# twomics_sw_led.net
KiCad netlist of a schematic drawn in EAGLE
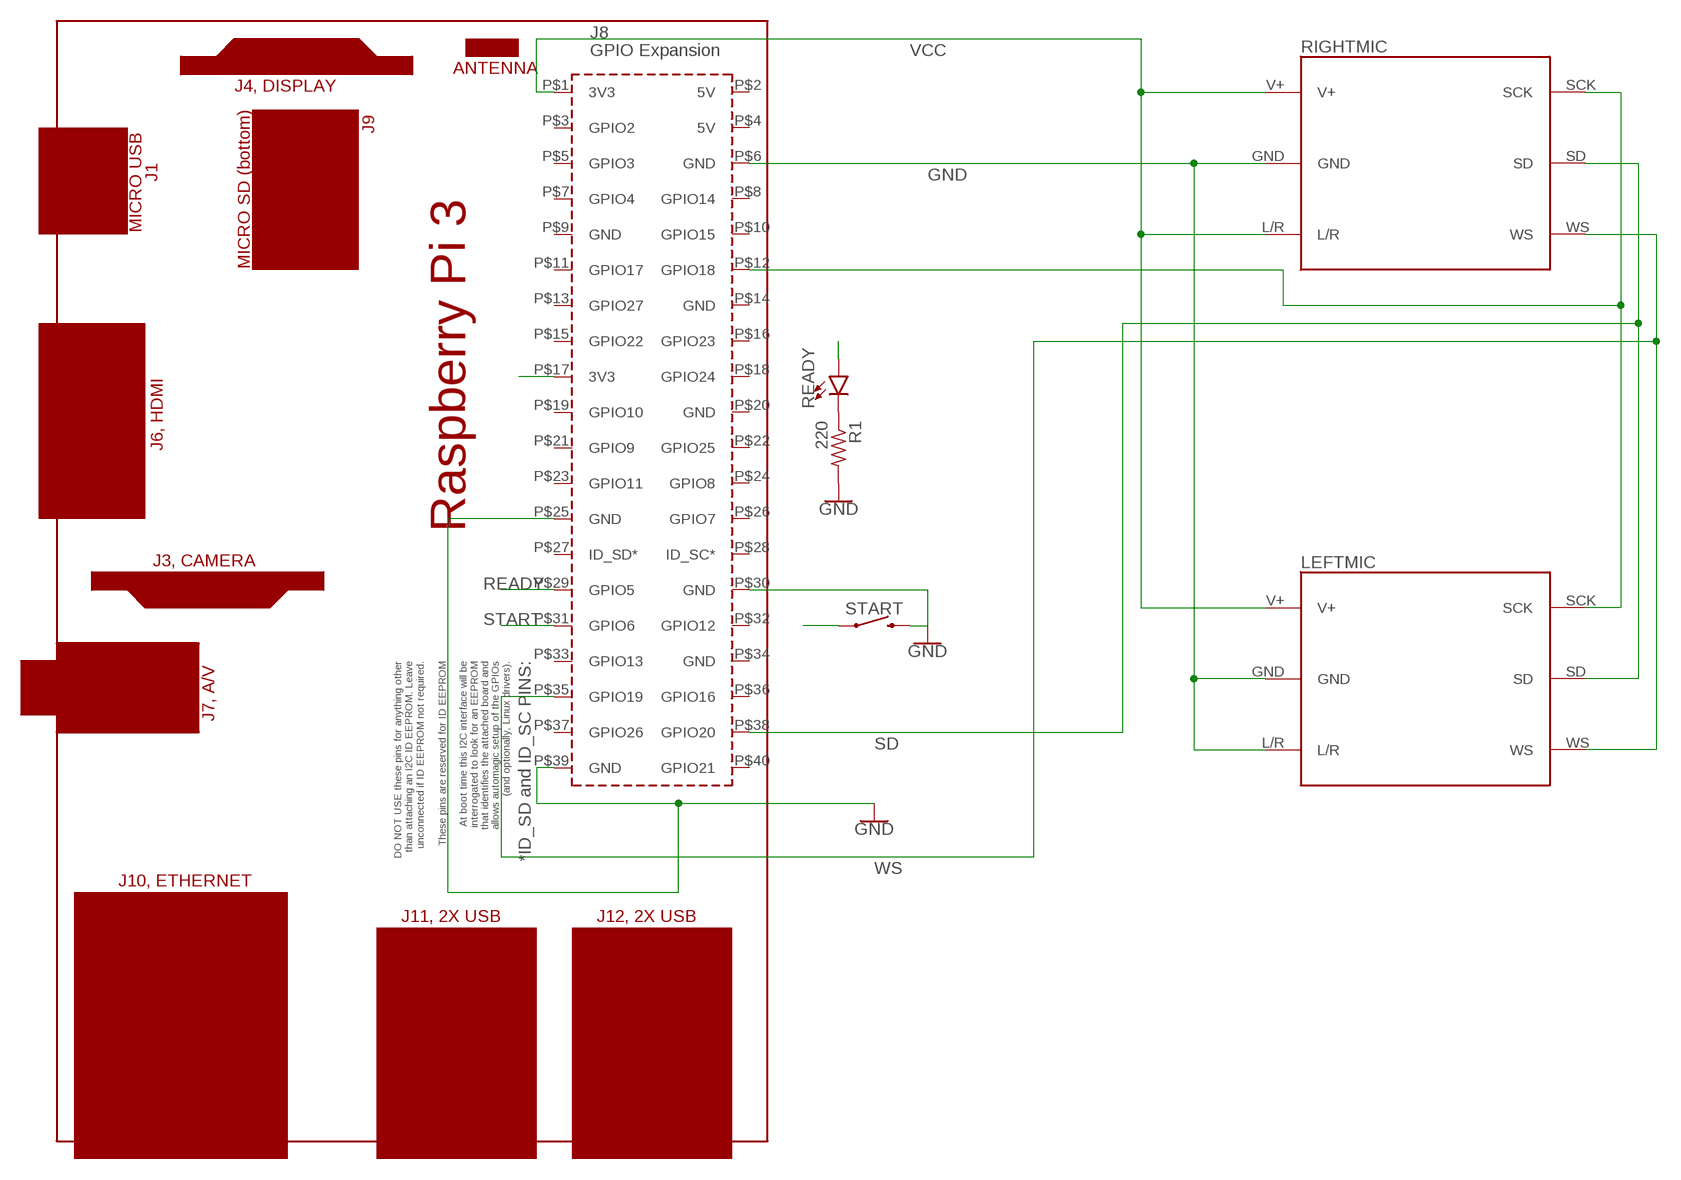
[diagram p0: schematic, sheet 1]

(export (version "E")
  (design (tool "Eeschema 10.0.6"))
  (components
    (comp (ref "LEFTMIC")
      (value "EMMIC-ICS43432")
      (footprint "eagle-import:PTH")
      (libsource (lib "eagle-import") (part "EMMIC-ICS43432"))
    )
    (comp (ref "PCB1")
      (value "RPI3_40_PIN")
      (footprint "eagle-import:40_PIN")
      (libsource (lib "eagle-import") (part "RPI3_40_PIN"))
    )
    (comp (ref "R1")
      (value "220")
      (footprint "eagle-import:0207_7")
      (libsource (lib "eagle-import") (part "R-US_0207/7"))
    )
    (comp (ref "READY")
      (value "LED3MM")
      (footprint "eagle-import:LED_3MM")
      (libsource (lib "eagle-import") (part "LED3MM"))
    )
    (comp (ref "RIGHTMIC")
      (value "EMMIC-ICS43432")
      (footprint "eagle-import:PTH")
      (libsource (lib "eagle-import") (part "EMMIC-ICS43432"))
    )
    (comp (ref "START")
      (value "MOMENTARY-SWITCH-SPST-PTH-6.0MM")
      (footprint "eagle-import:TACTILE_SWITCH_PTH_6.0MM")
      (libsource (lib "eagle-import") (part "MOMENTARY-SWITCH-SPST-PTH-6.0MM"))
    )
  )
  (nets
    (net (code "1") (name "/READY") (class "Default")
      (node (ref "PCB1") (pin "P$29") (pinfunction "GPIO5_P$29") (pintype "bidirectional"))
      (node (ref "READY") (pin "A") (pinfunction "A_A") (pintype "passive"))
    )
    (net (code "2") (name "/SD") (class "Default")
      (node (ref "LEFTMIC") (pin "SD") (pinfunction "SD_SD") (pintype "bidirectional"))
      (node (ref "PCB1") (pin "P$38") (pinfunction "GPIO20_P$38") (pintype "bidirectional"))
      (node (ref "RIGHTMIC") (pin "SD") (pinfunction "SD_SD") (pintype "bidirectional"))
    )
    (net (code "3") (name "/START") (class "Default")
      (node (ref "PCB1") (pin "P$31") (pinfunction "GPIO6_P$31") (pintype "bidirectional"))
      (node (ref "START") (pin "1") (pinfunction "1_1") (pintype "passive"))
    )
    (net (code "4") (name "/VCC") (class "Default")
      (node (ref "LEFTMIC") (pin "V+") (pinfunction "V+_V+") (pintype "bidirectional"))
      (node (ref "PCB1") (pin "P$1") (pinfunction "3V3_P$1") (pintype "bidirectional"))
      (node (ref "PCB1") (pin "P$17") (pinfunction "3V3_P$17") (pintype "bidirectional"))
      (node (ref "RIGHTMIC") (pin "L/R") (pinfunction "L/R_L/R") (pintype "bidirectional"))
      (node (ref "RIGHTMIC") (pin "V+") (pinfunction "V+_V+") (pintype "bidirectional"))
    )
    (net (code "5") (name "/WS") (class "Default")
      (node (ref "LEFTMIC") (pin "WS") (pinfunction "WS_WS") (pintype "bidirectional"))
      (node (ref "PCB1") (pin "P$35") (pinfunction "GPIO19_P$35") (pintype "bidirectional"))
      (node (ref "RIGHTMIC") (pin "WS") (pinfunction "WS_WS") (pintype "bidirectional"))
    )
    (net (code "6") (name "GND") (class "Default")
      (node (ref "LEFTMIC") (pin "GND") (pinfunction "GND_GND") (pintype "bidirectional"))
      (node (ref "LEFTMIC") (pin "L/R") (pinfunction "L/R_L/R") (pintype "bidirectional"))
      (node (ref "PCB1") (pin "P$25") (pinfunction "GND_P$25") (pintype "bidirectional"))
      (node (ref "PCB1") (pin "P$30") (pinfunction "GND_P$30") (pintype "bidirectional"))
      (node (ref "PCB1") (pin "P$39") (pinfunction "GND_P$39") (pintype "bidirectional"))
      (node (ref "PCB1") (pin "P$6") (pinfunction "GND_P$6") (pintype "bidirectional"))
      (node (ref "R1") (pin "2") (pinfunction "2_2") (pintype "passive"))
      (node (ref "RIGHTMIC") (pin "GND") (pinfunction "GND_GND") (pintype "bidirectional"))
      (node (ref "START") (pin "3") (pinfunction "2_3") (pintype "passive"))
    )
    (net (code "7") (name "Net-(PCB1-GPIO18)") (class "Default")
      (node (ref "LEFTMIC") (pin "SCK") (pinfunction "SCK_SCK") (pintype "bidirectional"))
      (node (ref "PCB1") (pin "P$12") (pinfunction "GPIO18_P$12") (pintype "bidirectional"))
      (node (ref "RIGHTMIC") (pin "SCK") (pinfunction "SCK_SCK") (pintype "bidirectional"))
    )
    (net (code "8") (name "Net-(READY-C)") (class "Default")
      (node (ref "R1") (pin "1") (pinfunction "1_1") (pintype "passive"))
      (node (ref "READY") (pin "K") (pinfunction "C_K") (pintype "passive"))
    )
    (net (code "9") (name "unconnected-(PCB1-5V-PadP$2)") (class "Default")
      (node (ref "PCB1") (pin "P$2") (pinfunction "5V_P$2") (pintype "bidirectional"))
    )
    (net (code "10") (name "unconnected-(PCB1-5V-PadP$4)") (class "Default")
      (node (ref "PCB1") (pin "P$4") (pinfunction "5V_P$4") (pintype "bidirectional"))
    )
    (net (code "11") (name "unconnected-(PCB1-GND-PadP$9)") (class "Default")
      (node (ref "PCB1") (pin "P$9") (pinfunction "GND_P$9") (pintype "bidirectional"))
    )
    (net (code "12") (name "unconnected-(PCB1-GND-PadP$14)") (class "Default")
      (node (ref "PCB1") (pin "P$14") (pinfunction "GND_P$14") (pintype "bidirectional"))
    )
    (net (code "13") (name "unconnected-(PCB1-GND-PadP$20)") (class "Default")
      (node (ref "PCB1") (pin "P$20") (pinfunction "GND_P$20") (pintype "bidirectional"))
    )
    (net (code "14") (name "unconnected-(PCB1-GND-PadP$34)") (class "Default")
      (node (ref "PCB1") (pin "P$34") (pinfunction "GND_P$34") (pintype "bidirectional"))
    )
    (net (code "15") (name "unconnected-(PCB1-GPIO2-PadP$3)") (class "Default")
      (node (ref "PCB1") (pin "P$3") (pinfunction "GPIO2_P$3") (pintype "bidirectional"))
    )
    (net (code "16") (name "unconnected-(PCB1-GPIO3-PadP$5)") (class "Default")
      (node (ref "PCB1") (pin "P$5") (pinfunction "GPIO3_P$5") (pintype "bidirectional"))
    )
    (net (code "17") (name "unconnected-(PCB1-GPIO4-PadP$7)") (class "Default")
      (node (ref "PCB1") (pin "P$7") (pinfunction "GPIO4_P$7") (pintype "bidirectional"))
    )
    (net (code "18") (name "unconnected-(PCB1-GPIO7-PadP$26)") (class "Default")
      (node (ref "PCB1") (pin "P$26") (pinfunction "GPIO7_P$26") (pintype "bidirectional"))
    )
    (net (code "19") (name "unconnected-(PCB1-GPIO8-PadP$24)") (class "Default")
      (node (ref "PCB1") (pin "P$24") (pinfunction "GPIO8_P$24") (pintype "bidirectional"))
    )
    (net (code "20") (name "unconnected-(PCB1-GPIO9-PadP$21)") (class "Default")
      (node (ref "PCB1") (pin "P$21") (pinfunction "GPIO9_P$21") (pintype "bidirectional"))
    )
    (net (code "21") (name "unconnected-(PCB1-GPIO10-PadP$19)") (class "Default")
      (node (ref "PCB1") (pin "P$19") (pinfunction "GPIO10_P$19") (pintype "bidirectional"))
    )
    (net (code "22") (name "unconnected-(PCB1-GPIO11-PadP$23)") (class "Default")
      (node (ref "PCB1") (pin "P$23") (pinfunction "GPIO11_P$23") (pintype "bidirectional"))
    )
    (net (code "23") (name "unconnected-(PCB1-GPIO12-PadP$32)") (class "Default")
      (node (ref "PCB1") (pin "P$32") (pinfunction "GPIO12_P$32") (pintype "bidirectional"))
    )
    (net (code "24") (name "unconnected-(PCB1-GPIO13-PadP$33)") (class "Default")
      (node (ref "PCB1") (pin "P$33") (pinfunction "GPIO13_P$33") (pintype "bidirectional"))
    )
    (net (code "25") (name "unconnected-(PCB1-GPIO14-PadP$8)") (class "Default")
      (node (ref "PCB1") (pin "P$8") (pinfunction "GPIO14_P$8") (pintype "bidirectional"))
    )
    (net (code "26") (name "unconnected-(PCB1-GPIO15-PadP$10)") (class "Default")
      (node (ref "PCB1") (pin "P$10") (pinfunction "GPIO15_P$10") (pintype "bidirectional"))
    )
    (net (code "27") (name "unconnected-(PCB1-GPIO16-PadP$36)") (class "Default")
      (node (ref "PCB1") (pin "P$36") (pinfunction "GPIO16_P$36") (pintype "bidirectional"))
    )
    (net (code "28") (name "unconnected-(PCB1-GPIO17-PadP$11)") (class "Default")
      (node (ref "PCB1") (pin "P$11") (pinfunction "GPIO17_P$11") (pintype "bidirectional"))
    )
    (net (code "29") (name "unconnected-(PCB1-GPIO21-PadP$40)") (class "Default")
      (node (ref "PCB1") (pin "P$40") (pinfunction "GPIO21_P$40") (pintype "bidirectional"))
    )
    (net (code "30") (name "unconnected-(PCB1-GPIO22-PadP$15)") (class "Default")
      (node (ref "PCB1") (pin "P$15") (pinfunction "GPIO22_P$15") (pintype "bidirectional"))
    )
    (net (code "31") (name "unconnected-(PCB1-GPIO23-PadP$16)") (class "Default")
      (node (ref "PCB1") (pin "P$16") (pinfunction "GPIO23_P$16") (pintype "bidirectional"))
    )
    (net (code "32") (name "unconnected-(PCB1-GPIO24-PadP$18)") (class "Default")
      (node (ref "PCB1") (pin "P$18") (pinfunction "GPIO24_P$18") (pintype "bidirectional"))
    )
    (net (code "33") (name "unconnected-(PCB1-GPIO25-PadP$22)") (class "Default")
      (node (ref "PCB1") (pin "P$22") (pinfunction "GPIO25_P$22") (pintype "bidirectional"))
    )
    (net (code "34") (name "unconnected-(PCB1-GPIO26-PadP$37)") (class "Default")
      (node (ref "PCB1") (pin "P$37") (pinfunction "GPIO26_P$37") (pintype "bidirectional"))
    )
    (net (code "35") (name "unconnected-(PCB1-GPIO27-PadP$13)") (class "Default")
      (node (ref "PCB1") (pin "P$13") (pinfunction "GPIO27_P$13") (pintype "bidirectional"))
    )
    (net (code "36") (name "unconnected-(PCB1-ID_SC*-PadP$28)") (class "Default")
      (node (ref "PCB1") (pin "P$28") (pinfunction "ID_SC*_P$28") (pintype "bidirectional"))
    )
    (net (code "37") (name "unconnected-(PCB1-ID_SD*-PadP$27)") (class "Default")
      (node (ref "PCB1") (pin "P$27") (pinfunction "ID_SD*_P$27") (pintype "bidirectional"))
    )
  )
)
